# STM32_EDITED.net
KiCad netlist of a schematic drawn in Altium Designer
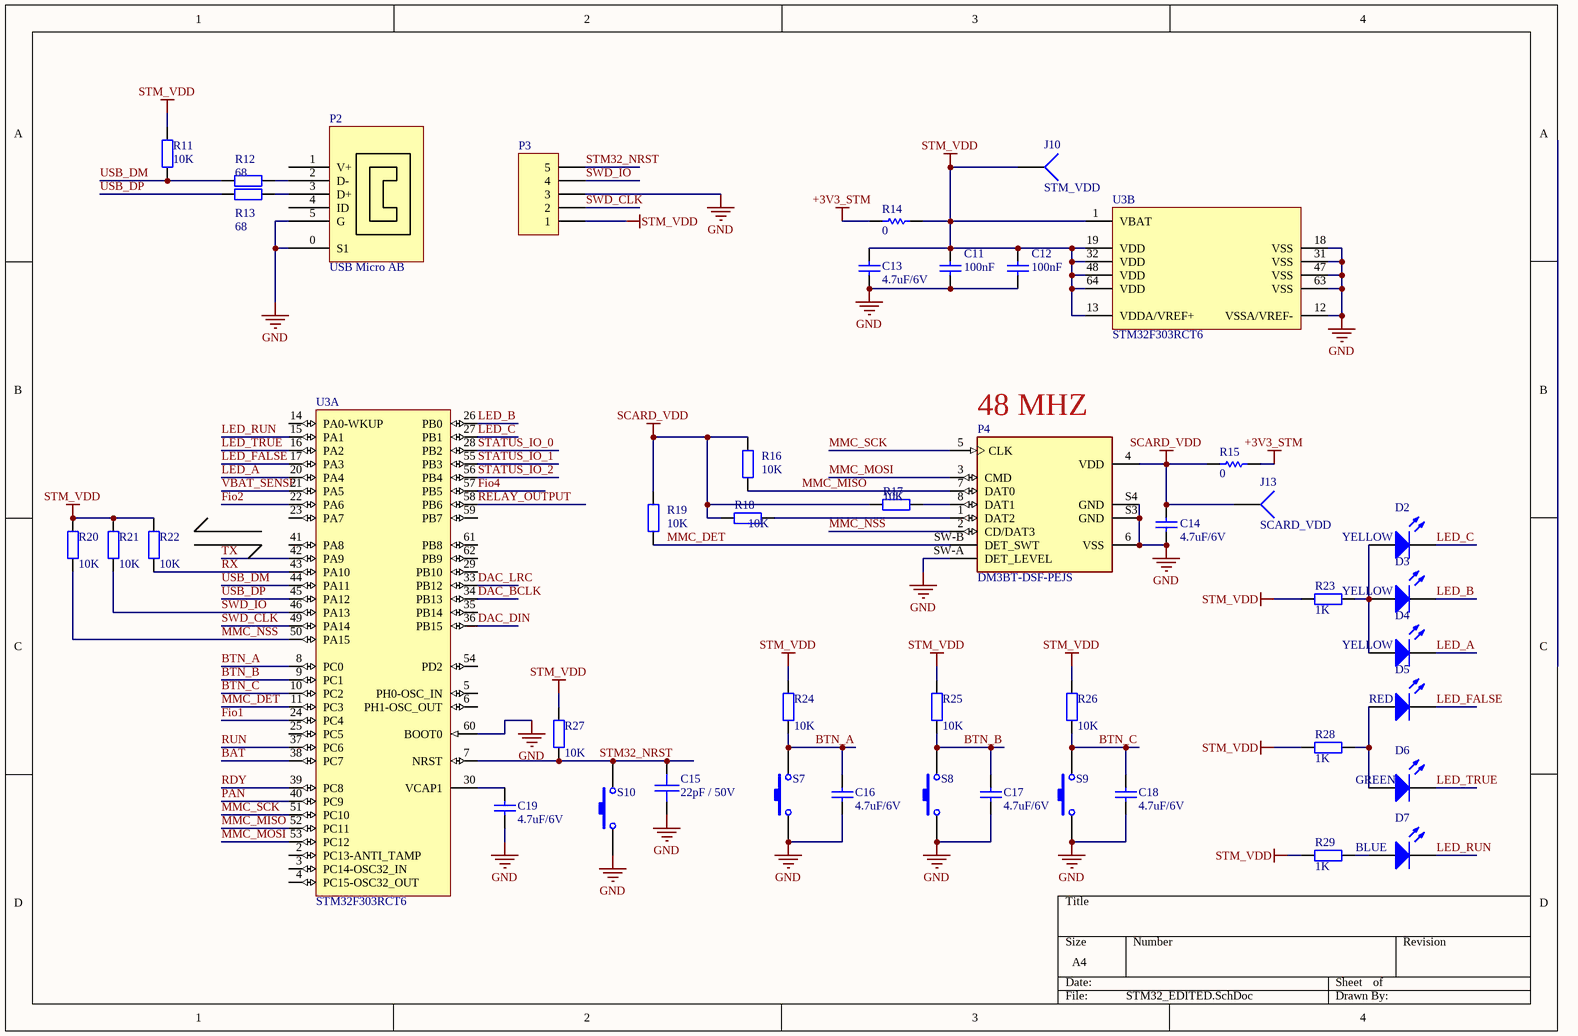
[diagram p0: STM32_EDITED.SchDoc]

(export (version "E")
  (design (tool "Eeschema 10.0.6"))
  (components
    (comp (ref "C11")
      (value "100nF")
      (footprint "CR2012-0805")
      (description "Capacitor")
      (fields (field (name "PUBLISHER") "Altium Limited"))
      (libsource (lib "Miscellaneous Devices") (part "Cap"))
    )
    (comp (ref "C12")
      (value "100nF")
      (footprint "CR2012-0805")
      (description "Capacitor")
      (fields (field (name "PUBLISHER") "Altium Limited"))
      (libsource (lib "Miscellaneous Devices") (part "Cap"))
    )
    (comp (ref "C13")
      (value "4.7uF/6V")
      (footprint "CR2012-0805")
      (description "Capacitor (Semiconductor SIM Model)")
      (fields (field (name "PUBLISHER") "Altium Limited"))
      (libsource (lib "passive") (part "Cap Semi"))
    )
    (comp (ref "C14")
      (value "4.7uF/6V")
      (footprint "CR2012-0805")
      (description "Capacitor")
      (fields (field (name "PUBLISHER") "Altium Limited"))
      (libsource (lib "Miscellaneous Devices") (part "Cap"))
    )
    (comp (ref "C15")
      (value "22pF / 50V")
      (footprint "CR2012-0805")
      (description "Surface mount capacitor 0402")
      (libsource (lib "Vowstar_Basic_Device") (part "SMT_C_0402"))
    )
    (comp (ref "C16")
      (value "4.7uF/6V")
      (footprint "CR2012-0805")
      (description "Capacitor (Semiconductor SIM Model)")
      (fields (field (name "PUBLISHER") "Altium Limited"))
      (libsource (lib "passive") (part "Cap Semi"))
    )
    (comp (ref "C17")
      (value "4.7uF/6V")
      (footprint "CR2012-0805")
      (description "Capacitor (Semiconductor SIM Model)")
      (fields (field (name "PUBLISHER") "Altium Limited"))
      (libsource (lib "passive") (part "Cap Semi"))
    )
    (comp (ref "C18")
      (value "4.7uF/6V")
      (footprint "CR2012-0805")
      (description "Capacitor (Semiconductor SIM Model)")
      (fields (field (name "PUBLISHER") "Altium Limited"))
      (libsource (lib "passive") (part "Cap Semi"))
    )
    (comp (ref "C19")
      (value "4.7uF/6V")
      (footprint "CR2012-0805")
      (description "Capacitor (Semiconductor SIM Model)")
      (fields (field (name "PUBLISHER") "Altium Limited"))
      (libsource (lib "passive") (part "Cap Semi"))
    )
    (comp (ref "D2")
      (value "YELLOW")
      (footprint "LED1206")
      (description "Typical INFRARED GaAs LED")
      (fields (field (name "PUBLISHER") "Altium Limited"))
      (libsource (lib "Miscellaneous Devices") (part "LED0"))
    )
    (comp (ref "D3")
      (value "YELLOW")
      (footprint "LED1206")
      (description "Typical INFRARED GaAs LED")
      (fields (field (name "PUBLISHER") "Altium Limited"))
      (libsource (lib "Miscellaneous Devices") (part "LED0"))
    )
    (comp (ref "D4")
      (value "YELLOW")
      (footprint "LED1206")
      (description "Typical INFRARED GaAs LED")
      (fields (field (name "PUBLISHER") "Altium Limited"))
      (libsource (lib "Miscellaneous Devices") (part "LED0"))
    )
    (comp (ref "D5")
      (value "RED")
      (footprint "LED1206")
      (description "Typical INFRARED GaAs LED")
      (fields (field (name "PUBLISHER") "Altium Limited"))
      (libsource (lib "Miscellaneous Devices") (part "LED0"))
    )
    (comp (ref "D6")
      (value "GREEN")
      (footprint "LED1206")
      (description "Typical INFRARED GaAs LED")
      (fields (field (name "PUBLISHER") "Altium Limited"))
      (libsource (lib "Miscellaneous Devices") (part "LED0"))
    )
    (comp (ref "D7")
      (value "BLUE")
      (footprint "LED1206")
      (description "Typical INFRARED GaAs LED")
      (fields (field (name "PUBLISHER") "Altium Limited"))
      (libsource (lib "Miscellaneous Devices") (part "LED0"))
    )
    (comp (ref "J10")
      (value "STM_VDD")
      (footprint "PIN1")
      (description "Socket")
      (fields (field (name "PUBLISHER") "Altium Limited"))
      (libsource (lib "Miscellaneous Connectors") (part "Socket"))
    )
    (comp (ref "J13")
      (value "SCARD_VDD")
      (footprint "PIN1")
      (description "Socket")
      (fields (field (name "PUBLISHER") "Altium Limited"))
      (libsource (lib "Miscellaneous Connectors") (part "Socket"))
    )
    (comp (ref "P2")
      (value "USB Micro AB")
      (footprint "USB_MICRO_wi_LEG")
      (description "USB Micro AB connector")
      (libsource (lib "passive") (part "USB Micro AB"))
    )
    (comp (ref "P3")
      (value "SWD_STM32")
      (footprint "HDR1X5")
      (description "Header, 5-Pin")
      (fields (field (name "PUBLISHER") "Altium Limited"))
      (libsource (lib "Miscellaneous Connectors") (part "Header 5"))
    )
    (comp (ref "P4")
      (value "DM3BT-DSF-PEJS")
      (footprint "HRS_DM3BT-DSF-PEJS")
      (description "10 _8 + 2_ microSDâ„¢ Surface Mount, Right Angle Gold")
      (fields (field (name "MP") "502570-0893") (field (name "MF") "Molex"))
      (libsource (lib "passive") (part "DM3BT-DSF-PEJS"))
    )
    (comp (ref "R11")
      (value "10K")
      (footprint "CR2012-0805")
      (description "Resistor")
      (fields (field (name "PUBLISHER") "Altium Limited"))
      (libsource (lib "") (part "Res2_1"))
    )
    (comp (ref "R12")
      (value "68")
      (footprint "CR2012-0805")
      (description "Resistor")
      (fields (field (name "PUBLISHER") "Altium Limited"))
      (libsource (lib "Miscellaneous Devices") (part "Res2"))
    )
    (comp (ref "R13")
      (value "68")
      (footprint "CR2012-0805")
      (description "Resistor")
      (fields (field (name "PUBLISHER") "Altium Limited"))
      (libsource (lib "Miscellaneous Devices") (part "Res2"))
    )
    (comp (ref "R14")
      (value "0")
      (footprint "JP1_SMD")
      (description "Semiconductor Resistor")
      (fields (field (name "PUBLISHER") "Altium Limited"))
      (libsource (lib "passive") (part "Res Semi"))
    )
    (comp (ref "R15")
      (value "0")
      (footprint "JP1_SMD")
      (description "Semiconductor Resistor")
      (fields (field (name "PUBLISHER") "Altium Limited"))
      (libsource (lib "passive") (part "Res Semi"))
    )
    (comp (ref "R16")
      (value "10K")
      (footprint "CR2012-0805")
      (description "Resistor")
      (fields (field (name "PUBLISHER") "Altium Limited"))
      (libsource (lib "") (part "Res2_1"))
    )
    (comp (ref "R17")
      (value "10K")
      (footprint "CR2012-0805")
      (description "Resistor")
      (fields (field (name "PUBLISHER") "Altium Limited"))
      (libsource (lib "Miscellaneous Devices") (part "Res2"))
    )
    (comp (ref "R18")
      (value "10K")
      (footprint "CR2012-0805")
      (description "Resistor")
      (fields (field (name "PUBLISHER") "Altium Limited"))
      (libsource (lib "Miscellaneous Devices") (part "Res2"))
    )
    (comp (ref "R19")
      (value "10K")
      (footprint "CR2012-0805")
      (description "Resistor")
      (fields (field (name "PUBLISHER") "Altium Limited"))
      (libsource (lib "") (part "Res2_1"))
    )
    (comp (ref "R20")
      (value "10K")
      (footprint "CR2012-0805")
      (description "Resistor")
      (fields (field (name "PUBLISHER") "Altium Limited"))
      (libsource (lib "") (part "Res2_2"))
    )
    (comp (ref "R21")
      (value "10K")
      (footprint "CR2012-0805")
      (description "Resistor")
      (fields (field (name "PUBLISHER") "Altium Limited"))
      (libsource (lib "") (part "Res2_2"))
    )
    (comp (ref "R22")
      (value "10K")
      (footprint "CR2012-0805")
      (description "Resistor")
      (fields (field (name "PUBLISHER") "Altium Limited"))
      (libsource (lib "") (part "Res2_2"))
    )
    (comp (ref "R23")
      (value "1K")
      (footprint "CR2012-0805")
      (description "Resistor")
      (fields (field (name "PUBLISHER") "Altium Limited"))
      (libsource (lib "") (part "Res2_3"))
    )
    (comp (ref "R24")
      (value "10K")
      (footprint "CR2012-0805")
      (description "Resistor")
      (fields (field (name "PUBLISHER") "Altium Limited"))
      (libsource (lib "") (part "Res2_2"))
    )
    (comp (ref "R25")
      (value "10K")
      (footprint "CR2012-0805")
      (description "Resistor")
      (fields (field (name "PUBLISHER") "Altium Limited"))
      (libsource (lib "") (part "Res2_2"))
    )
    (comp (ref "R26")
      (value "10K")
      (footprint "CR2012-0805")
      (description "Resistor")
      (fields (field (name "PUBLISHER") "Altium Limited"))
      (libsource (lib "") (part "Res2_2"))
    )
    (comp (ref "R27")
      (value "10K")
      (footprint "CR2012-0805")
      (description "Resistor")
      (fields (field (name "PUBLISHER") "Altium Limited"))
      (libsource (lib "") (part "Res2_1"))
    )
    (comp (ref "R28")
      (value "1K")
      (footprint "CR2012-0805")
      (description "Resistor")
      (fields (field (name "PUBLISHER") "Altium Limited"))
      (libsource (lib "") (part "Res2_3"))
    )
    (comp (ref "R29")
      (value "1K")
      (footprint "CR2012-0805")
      (description "Resistor")
      (fields (field (name "PUBLISHER") "Altium Limited"))
      (libsource (lib "") (part "Res2_3"))
    )
    (comp (ref "S7")
      (value "SW-PB")
      (footprint "pushbutton")
      (description "Switch")
      (fields (field (name "PUBLISHER") "Altium Limited"))
      (libsource (lib "Miscellaneous Devices") (part "SW-PB"))
    )
    (comp (ref "S8")
      (value "SW-PB")
      (footprint "pushbutton")
      (description "Switch")
      (fields (field (name "PUBLISHER") "Altium Limited"))
      (libsource (lib "Miscellaneous Devices") (part "SW-PB"))
    )
    (comp (ref "S9")
      (value "SW-PB")
      (footprint "pushbutton")
      (description "Switch")
      (fields (field (name "PUBLISHER") "Altium Limited"))
      (libsource (lib "Miscellaneous Devices") (part "SW-PB"))
    )
    (comp (ref "S10")
      (value "SW-PB")
      (footprint "pushbutton")
      (description "Switch")
      (fields (field (name "PUBLISHER") "Altium Limited"))
      (libsource (lib "Miscellaneous Devices") (part "SW-PB"))
    )
    (comp (ref "U3")
      (value "STM32F303RCT6")
      (footprint "STM-LQFP64_N")
      (fields (field (name "MANUFACTURER") "STMicroelectronics") (field (name "PARTNUMBER") "STM32F401RCT6"))
      (libsource (lib "STMicroelectronics STM32 F4") (part "STM32F401RCT6"))
    )
  )
  (nets
    (net (code "1") (name "+3V3_STM") (class "Default")
      (node (ref "R14") (pin "1") (pinfunction "1_1") (pintype "passive"))
      (node (ref "R15") (pin "1") (pinfunction "1_1") (pintype "passive"))
    )
    (net (code "2") (name "/BAT") (class "Default")
      (node (ref "U3") (pin "38") (pinfunction "PC7_38") (pintype "bidirectional"))
    )
    (net (code "3") (name "/BTN_A") (class "Default")
      (node (ref "C16") (pin "2") (pinfunction "2_2") (pintype "passive"))
      (node (ref "R24") (pin "2") (pinfunction "2_2") (pintype "passive"))
      (node (ref "S7") (pin "2") (pinfunction "2_2") (pintype "passive"))
      (node (ref "U3") (pin "8") (pinfunction "PC0_8") (pintype "bidirectional"))
    )
    (net (code "4") (name "/BTN_B") (class "Default")
      (node (ref "C17") (pin "2") (pinfunction "2_2") (pintype "passive"))
      (node (ref "R25") (pin "2") (pinfunction "2_2") (pintype "passive"))
      (node (ref "S8") (pin "2") (pinfunction "2_2") (pintype "passive"))
      (node (ref "U3") (pin "9") (pinfunction "PC1_9") (pintype "bidirectional"))
    )
    (net (code "5") (name "/BTN_C") (class "Default")
      (node (ref "C18") (pin "2") (pinfunction "2_2") (pintype "passive"))
      (node (ref "R26") (pin "2") (pinfunction "2_2") (pintype "passive"))
      (node (ref "S9") (pin "2") (pinfunction "2_2") (pintype "passive"))
      (node (ref "U3") (pin "10") (pinfunction "PC2_10") (pintype "bidirectional"))
    )
    (net (code "6") (name "/DAC_BCLK") (class "Default")
      (node (ref "U3") (pin "34") (pinfunction "PB13_34") (pintype "bidirectional"))
    )
    (net (code "7") (name "/DAC_DIN") (class "Default")
      (node (ref "U3") (pin "36") (pinfunction "PB15_36") (pintype "bidirectional"))
    )
    (net (code "8") (name "/DAC_LRC") (class "Default")
      (node (ref "U3") (pin "33") (pinfunction "PB12_33") (pintype "bidirectional"))
    )
    (net (code "9") (name "/Fio1") (class "Default")
      (node (ref "U3") (pin "24") (pinfunction "PC4_24") (pintype "bidirectional"))
    )
    (net (code "10") (name "/Fio2") (class "Default")
      (node (ref "U3") (pin "22") (pinfunction "PA6_22") (pintype "bidirectional"))
    )
    (net (code "11") (name "/Fio4") (class "Default")
      (node (ref "U3") (pin "57") (pinfunction "PB5_57") (pintype "bidirectional"))
    )
    (net (code "12") (name "/LED_A") (class "Default")
      (node (ref "D4") (pin "K") (pinfunction "K_K") (pintype "passive"))
      (node (ref "U3") (pin "20") (pinfunction "PA4_20") (pintype "bidirectional"))
    )
    (net (code "13") (name "/LED_B") (class "Default")
      (node (ref "D3") (pin "K") (pinfunction "K_K") (pintype "passive"))
      (node (ref "U3") (pin "26") (pinfunction "PB0_26") (pintype "bidirectional"))
    )
    (net (code "14") (name "/LED_C") (class "Default")
      (node (ref "D2") (pin "K") (pinfunction "K_K") (pintype "passive"))
      (node (ref "U3") (pin "27") (pinfunction "PB1_27") (pintype "bidirectional"))
    )
    (net (code "15") (name "/LED_FALSE") (class "Default")
      (node (ref "D5") (pin "K") (pinfunction "K_K") (pintype "passive"))
      (node (ref "U3") (pin "17") (pinfunction "PA3_17") (pintype "bidirectional"))
    )
    (net (code "16") (name "/LED_RUN") (class "Default")
      (node (ref "D7") (pin "K") (pinfunction "K_K") (pintype "passive"))
      (node (ref "U3") (pin "15") (pinfunction "PA1_15") (pintype "bidirectional"))
    )
    (net (code "17") (name "/LED_TRUE") (class "Default")
      (node (ref "D6") (pin "K") (pinfunction "K_K") (pintype "passive"))
      (node (ref "U3") (pin "16") (pinfunction "PA2_16") (pintype "bidirectional"))
    )
    (net (code "18") (name "/MMC_DET") (class "Default")
      (node (ref "P4") (pin "SW-B") (pinfunction "DET_SWT_SW-B") (pintype "passive"))
      (node (ref "R19") (pin "1") (pinfunction "1_1") (pintype "passive"))
      (node (ref "U3") (pin "11") (pinfunction "PC3_11") (pintype "bidirectional"))
    )
    (net (code "19") (name "/MMC_MISO") (class "Default")
      (node (ref "P4") (pin "7") (pinfunction "DAT0_7") (pintype "bidirectional"))
      (node (ref "R16") (pin "1") (pinfunction "1_1") (pintype "passive"))
      (node (ref "U3") (pin "52") (pinfunction "PC11_52") (pintype "bidirectional"))
    )
    (net (code "20") (name "/MMC_MOSI") (class "Default")
      (node (ref "P4") (pin "3") (pinfunction "CMD_3") (pintype "bidirectional"))
      (node (ref "U3") (pin "53") (pinfunction "PC12_53") (pintype "bidirectional"))
    )
    (net (code "21") (name "/MMC_NSS") (class "Default")
      (node (ref "P4") (pin "2") (pinfunction "CD/DAT3_2") (pintype "bidirectional"))
      (node (ref "R20") (pin "2") (pinfunction "2_2") (pintype "passive"))
      (node (ref "U3") (pin "50") (pinfunction "PA15_50") (pintype "bidirectional"))
    )
    (net (code "22") (name "/MMC_SCK") (class "Default")
      (node (ref "P4") (pin "5") (pinfunction "CLK_5") (pintype "input"))
      (node (ref "U3") (pin "51") (pinfunction "PC10_51") (pintype "bidirectional"))
    )
    (net (code "23") (name "/PAN") (class "Default")
      (node (ref "U3") (pin "40") (pinfunction "PC9_40") (pintype "bidirectional"))
    )
    (net (code "24") (name "/RDY") (class "Default")
      (node (ref "U3") (pin "39") (pinfunction "PC8_39") (pintype "bidirectional"))
    )
    (net (code "25") (name "/RELAY_OUTPUT") (class "Default")
      (node (ref "U3") (pin "58") (pinfunction "PB6_58") (pintype "bidirectional"))
    )
    (net (code "26") (name "/RUN") (class "Default")
      (node (ref "U3") (pin "37") (pinfunction "PC6_37") (pintype "bidirectional"))
    )
    (net (code "27") (name "/RX") (class "Default")
      (node (ref "R22") (pin "2") (pinfunction "2_2") (pintype "passive"))
      (node (ref "U3") (pin "43") (pinfunction "PA10_43") (pintype "bidirectional"))
    )
    (net (code "28") (name "/STATUS_IO_0") (class "Default")
      (node (ref "U3") (pin "28") (pinfunction "PB2_28") (pintype "bidirectional"))
    )
    (net (code "29") (name "/STATUS_IO_1") (class "Default")
      (node (ref "U3") (pin "55") (pinfunction "PB3_55") (pintype "bidirectional"))
    )
    (net (code "30") (name "/STATUS_IO_2") (class "Default")
      (node (ref "U3") (pin "56") (pinfunction "PB4_56") (pintype "bidirectional"))
    )
    (net (code "31") (name "/STM32_NRST") (class "Default")
      (node (ref "C15") (pin "1") (pinfunction "1_1") (pintype "passive"))
      (node (ref "P3") (pin "5") (pinfunction "5_5") (pintype "passive"))
      (node (ref "R27") (pin "1") (pinfunction "1_1") (pintype "passive"))
      (node (ref "S10") (pin "2") (pinfunction "2_2") (pintype "passive"))
      (node (ref "U3") (pin "7") (pinfunction "NRST_7") (pintype "bidirectional"))
    )
    (net (code "32") (name "/SWD_CLK") (class "Default")
      (node (ref "P3") (pin "2") (pinfunction "2_2") (pintype "passive"))
      (node (ref "U3") (pin "49") (pinfunction "PA14_49") (pintype "bidirectional"))
    )
    (net (code "33") (name "/SWD_IO") (class "Default")
      (node (ref "P3") (pin "4") (pinfunction "4_4") (pintype "passive"))
      (node (ref "R21") (pin "2") (pinfunction "2_2") (pintype "passive"))
      (node (ref "U3") (pin "46") (pinfunction "PA13_46") (pintype "bidirectional"))
    )
    (net (code "34") (name "/TX") (class "Default")
      (node (ref "U3") (pin "42") (pinfunction "PA9_42") (pintype "bidirectional"))
    )
    (net (code "35") (name "/USB_DM") (class "Default")
      (node (ref "R11") (pin "1") (pinfunction "1_1") (pintype "passive"))
      (node (ref "R12") (pin "1") (pinfunction "1_1") (pintype "passive"))
      (node (ref "U3") (pin "44") (pinfunction "PA11_44") (pintype "bidirectional"))
    )
    (net (code "36") (name "/USB_DP") (class "Default")
      (node (ref "R13") (pin "1") (pinfunction "1_1") (pintype "passive"))
      (node (ref "U3") (pin "45") (pinfunction "PA12_45") (pintype "bidirectional"))
    )
    (net (code "37") (name "/VBAT_SENSE") (class "Default")
      (node (ref "U3") (pin "21") (pinfunction "PA5_21") (pintype "bidirectional"))
    )
    (net (code "38") (name "GND") (class "Default")
      (node (ref "C11") (pin "1") (pinfunction "1_1") (pintype "passive"))
      (node (ref "C12") (pin "1") (pinfunction "1_1") (pintype "passive"))
      (node (ref "C13") (pin "1") (pinfunction "1_1") (pintype "passive"))
      (node (ref "C14") (pin "1") (pinfunction "1_1") (pintype "passive"))
      (node (ref "C15") (pin "2") (pinfunction "2_2") (pintype "passive"))
      (node (ref "C16") (pin "1") (pinfunction "1_1") (pintype "passive"))
      (node (ref "C17") (pin "1") (pinfunction "1_1") (pintype "passive"))
      (node (ref "C18") (pin "1") (pinfunction "1_1") (pintype "passive"))
      (node (ref "C19") (pin "1") (pinfunction "1_1") (pintype "passive"))
      (node (ref "P2") (pin "0") (pinfunction "S1_0") (pintype "passive"))
      (node (ref "P2") (pin "5") (pinfunction "G_5") (pintype "passive"))
      (node (ref "P3") (pin "3") (pinfunction "3_3") (pintype "passive"))
      (node (ref "P4") (pin "6") (pinfunction "VSS_6") (pintype "power_in"))
      (node (ref "P4") (pin "S3") (pinfunction "GND_S3") (pintype "passive"))
      (node (ref "P4") (pin "S4") (pinfunction "GND_S4") (pintype "passive"))
      (node (ref "P4") (pin "SW-A") (pinfunction "DET_LEVEL_SW-A") (pintype "passive"))
      (node (ref "S10") (pin "1") (pinfunction "1_1") (pintype "passive"))
      (node (ref "S7") (pin "1") (pinfunction "1_1") (pintype "passive"))
      (node (ref "S8") (pin "1") (pinfunction "1_1") (pintype "passive"))
      (node (ref "S9") (pin "1") (pinfunction "1_1") (pintype "passive"))
      (node (ref "U3") (pin "12") (pinfunction "VSSA/VREF-_12") (pintype "power_in"))
      (node (ref "U3") (pin "18") (pinfunction "VSS_18") (pintype "power_in"))
      (node (ref "U3") (pin "31") (pinfunction "VSS_31") (pintype "power_in"))
      (node (ref "U3") (pin "47") (pinfunction "VSS_47") (pintype "power_in"))
      (node (ref "U3") (pin "60") (pinfunction "BOOT0_60") (pintype "input"))
      (node (ref "U3") (pin "63") (pinfunction "VSS_63") (pintype "power_in"))
    )
    (net (code "39") (name "Net-(D2-PadA)") (class "Default")
      (node (ref "D2") (pin "A") (pinfunction "A_A") (pintype "passive"))
      (node (ref "D3") (pin "A") (pinfunction "A_A") (pintype "passive"))
      (node (ref "D4") (pin "A") (pinfunction "A_A") (pintype "passive"))
      (node (ref "R23") (pin "1") (pinfunction "1_1") (pintype "passive"))
    )
    (net (code "40") (name "Net-(D5-PadA)") (class "Default")
      (node (ref "D5") (pin "A") (pinfunction "A_A") (pintype "passive"))
      (node (ref "D6") (pin "A") (pinfunction "A_A") (pintype "passive"))
      (node (ref "R28") (pin "1") (pinfunction "1_1") (pintype "passive"))
    )
    (net (code "41") (name "Net-(D7-PadA)") (class "Default")
      (node (ref "D7") (pin "A") (pinfunction "A_A") (pintype "passive"))
      (node (ref "R29") (pin "1") (pinfunction "1_1") (pintype "passive"))
    )
    (net (code "42") (name "Net-(P2-D+)") (class "Default")
      (node (ref "P2") (pin "3") (pinfunction "D+_3") (pintype "passive"))
      (node (ref "R13") (pin "2") (pinfunction "2_2") (pintype "passive"))
    )
    (net (code "43") (name "Net-(P2-D-)") (class "Default")
      (node (ref "P2") (pin "2") (pinfunction "D-_2") (pintype "passive"))
      (node (ref "R12") (pin "2") (pinfunction "2_2") (pintype "passive"))
    )
    (net (code "44") (name "Net-(P4-DAT1)") (class "Default")
      (node (ref "P4") (pin "8") (pinfunction "DAT1_8") (pintype "bidirectional"))
      (node (ref "R17") (pin "2") (pinfunction "2_2") (pintype "passive"))
    )
    (net (code "45") (name "Net-(P4-DAT2)") (class "Default")
      (node (ref "P4") (pin "1") (pinfunction "DAT2_1") (pintype "bidirectional"))
      (node (ref "R18") (pin "2") (pinfunction "2_2") (pintype "passive"))
    )
    (net (code "46") (name "Net-(U3A-VCAP1)") (class "Default")
      (node (ref "C19") (pin "2") (pinfunction "2_2") (pintype "passive"))
      (node (ref "U3") (pin "30") (pinfunction "VCAP1_30") (pintype "power_in"))
    )
    (net (code "47") (name "SCARD_VDD") (class "Default")
      (node (ref "C14") (pin "2") (pinfunction "2_2") (pintype "passive"))
      (node (ref "J13") (pin "1") (pinfunction "1_1") (pintype "passive"))
      (node (ref "P4") (pin "4") (pinfunction "VDD_4") (pintype "power_in"))
      (node (ref "R15") (pin "2") (pinfunction "2_2") (pintype "passive"))
      (node (ref "R16") (pin "2") (pinfunction "2_2") (pintype "passive"))
      (node (ref "R17") (pin "1") (pinfunction "1_1") (pintype "passive"))
      (node (ref "R18") (pin "1") (pinfunction "1_1") (pintype "passive"))
      (node (ref "R19") (pin "2") (pinfunction "2_2") (pintype "passive"))
    )
    (net (code "48") (name "STM_VDD") (class "Default")
      (node (ref "C11") (pin "2") (pinfunction "2_2") (pintype "passive"))
      (node (ref "C12") (pin "2") (pinfunction "2_2") (pintype "passive"))
      (node (ref "C13") (pin "2") (pinfunction "2_2") (pintype "passive"))
      (node (ref "J10") (pin "1") (pinfunction "1_1") (pintype "passive"))
      (node (ref "P3") (pin "1") (pinfunction "1_1") (pintype "passive"))
      (node (ref "R11") (pin "2") (pinfunction "2_2") (pintype "passive"))
      (node (ref "R14") (pin "2") (pinfunction "2_2") (pintype "passive"))
      (node (ref "R20") (pin "1") (pinfunction "1_1") (pintype "passive"))
      (node (ref "R21") (pin "1") (pinfunction "1_1") (pintype "passive"))
      (node (ref "R22") (pin "1") (pinfunction "1_1") (pintype "passive"))
      (node (ref "R23") (pin "2") (pinfunction "2_2") (pintype "passive"))
      (node (ref "R24") (pin "1") (pinfunction "1_1") (pintype "passive"))
      (node (ref "R25") (pin "1") (pinfunction "1_1") (pintype "passive"))
      (node (ref "R26") (pin "1") (pinfunction "1_1") (pintype "passive"))
      (node (ref "R27") (pin "2") (pinfunction "2_2") (pintype "passive"))
      (node (ref "R28") (pin "2") (pinfunction "2_2") (pintype "passive"))
      (node (ref "R29") (pin "2") (pinfunction "2_2") (pintype "passive"))
      (node (ref "U3") (pin "1") (pinfunction "VBAT_1") (pintype "power_in"))
      (node (ref "U3") (pin "13") (pinfunction "VDDA/VREF+_13") (pintype "power_in"))
      (node (ref "U3") (pin "19") (pinfunction "VDD_19") (pintype "power_in"))
      (node (ref "U3") (pin "32") (pinfunction "VDD_32") (pintype "power_in"))
      (node (ref "U3") (pin "48") (pinfunction "VDD_48") (pintype "power_in"))
      (node (ref "U3") (pin "64") (pinfunction "VDD_64") (pintype "power_in"))
    )
    (net (code "49") (name "unconnected-(P2-ID-Pad4)") (class "Default")
      (node (ref "P2") (pin "4") (pinfunction "ID_4") (pintype "passive"))
    )
    (net (code "50") (name "unconnected-(P2-V+-Pad1)") (class "Default")
      (node (ref "P2") (pin "1") (pinfunction "V+_1") (pintype "passive"))
    )
    (net (code "51") (name "unconnected-(U3A-PA0-WKUP-Pad14)") (class "Default")
      (node (ref "U3") (pin "14") (pinfunction "PA0-WKUP_14") (pintype "bidirectional"))
    )
    (net (code "52") (name "unconnected-(U3A-PA7-Pad23)") (class "Default")
      (node (ref "U3") (pin "23") (pinfunction "PA7_23") (pintype "bidirectional"))
    )
    (net (code "53") (name "unconnected-(U3A-PA8-Pad41)") (class "Default")
      (node (ref "U3") (pin "41") (pinfunction "PA8_41") (pintype "bidirectional"))
    )
    (net (code "54") (name "unconnected-(U3A-PB7-Pad59)") (class "Default")
      (node (ref "U3") (pin "59") (pinfunction "PB7_59") (pintype "bidirectional"))
    )
    (net (code "55") (name "unconnected-(U3A-PB8-Pad61)") (class "Default")
      (node (ref "U3") (pin "61") (pinfunction "PB8_61") (pintype "bidirectional"))
    )
    (net (code "56") (name "unconnected-(U3A-PB9-Pad62)") (class "Default")
      (node (ref "U3") (pin "62") (pinfunction "PB9_62") (pintype "bidirectional"))
    )
    (net (code "57") (name "unconnected-(U3A-PB10-Pad29)") (class "Default")
      (node (ref "U3") (pin "29") (pinfunction "PB10_29") (pintype "bidirectional"))
    )
    (net (code "58") (name "unconnected-(U3A-PB14-Pad35)") (class "Default")
      (node (ref "U3") (pin "35") (pinfunction "PB14_35") (pintype "bidirectional"))
    )
    (net (code "59") (name "unconnected-(U3A-PC5-Pad25)") (class "Default")
      (node (ref "U3") (pin "25") (pinfunction "PC5_25") (pintype "bidirectional"))
    )
    (net (code "60") (name "unconnected-(U3A-PC13-ANTI_TAMP-Pad2)") (class "Default")
      (node (ref "U3") (pin "2") (pinfunction "PC13-ANTI_TAMP_2") (pintype "bidirectional"))
    )
    (net (code "61") (name "unconnected-(U3A-PC14-OSC32_IN-Pad3)") (class "Default")
      (node (ref "U3") (pin "3") (pinfunction "PC14-OSC32_IN_3") (pintype "bidirectional"))
    )
    (net (code "62") (name "unconnected-(U3A-PC15-OSC32_OUT-Pad4)") (class "Default")
      (node (ref "U3") (pin "4") (pinfunction "PC15-OSC32_OUT_4") (pintype "bidirectional"))
    )
    (net (code "63") (name "unconnected-(U3A-PD2-Pad54)") (class "Default")
      (node (ref "U3") (pin "54") (pinfunction "PD2_54") (pintype "bidirectional"))
    )
    (net (code "64") (name "unconnected-(U3A-PH0-OSC_IN-Pad5)") (class "Default")
      (node (ref "U3") (pin "5") (pinfunction "PH0-OSC_IN_5") (pintype "bidirectional"))
    )
    (net (code "65") (name "unconnected-(U3A-PH1-OSC_OUT-Pad6)") (class "Default")
      (node (ref "U3") (pin "6") (pinfunction "PH1-OSC_OUT_6") (pintype "bidirectional"))
    )
  )
)
